# 1_main.net
KiCad netlist of a schematic drawn in Altium Designer
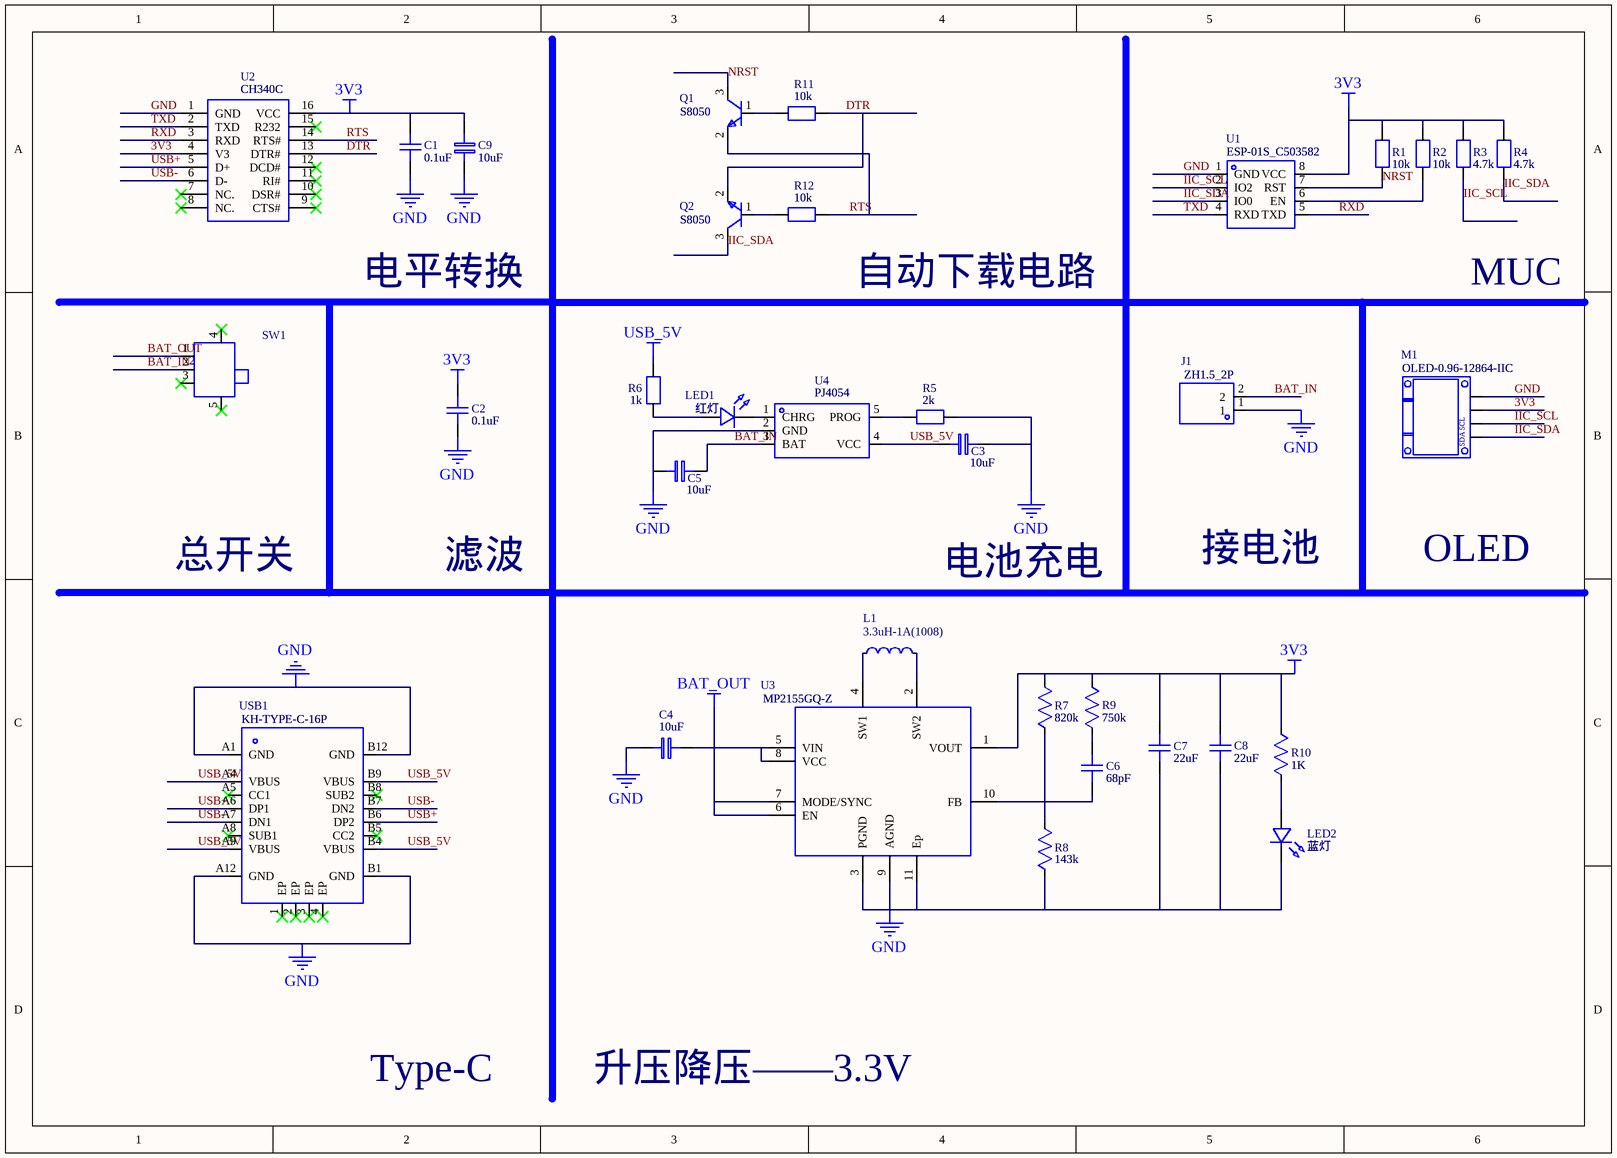
[diagram p0: 1_main.schdoc]

(export (version "E")
  (design (tool "Eeschema 10.0.6"))
  (components
    (comp (ref "C1")
      (value "0.1uF")
      (fields (field (name "NAME") "0.1uF"))
      (libsource (lib "altium-import") (part "root_1_0.1uF_"))
    )
    (comp (ref "C2")
      (value "0.1uF")
      (fields (field (name "NAME") "0.1uF"))
      (libsource (lib "altium-import") (part "root_1_0.1uF_C0805_"))
    )
    (comp (ref "C3")
      (value "10uF")
      (fields (field (name "NAME") "10uF"))
      (libsource (lib "altium-import") (part "root_0_10uF_"))
    )
    (comp (ref "C4")
      (value "10uF")
      (fields (field (name "NAME") "10uF"))
      (libsource (lib "altium-import") (part "root_0_10uF_C0805_"))
    )
    (comp (ref "C5")
      (value "10uF")
      (fields (field (name "NAME") "10uF"))
      (libsource (lib "altium-import") (part "root_0_10uF_C0805_"))
    )
    (comp (ref "C6")
      (value "68pF")
      (fields (field (name "NAME") "68pF"))
      (libsource (lib "altium-import") (part "root_1_68pF_"))
    )
    (comp (ref "C7")
      (value "22uF")
      (fields (field (name "NAME") "22uF"))
      (libsource (lib "altium-import") (part "root_1_22uF_"))
    )
    (comp (ref "C8")
      (value "22uF")
      (fields (field (name "NAME") "22uF"))
      (libsource (lib "altium-import") (part "root_1_22uF_C0805_"))
    )
    (comp (ref "C9")
      (value "10uF")
      (fields (field (name "NAME") "10uF"))
      (libsource (lib "altium-import") (part "root_1_10uF_C0805_"))
    )
    (comp (ref "J1")
      (value "ZH1.5_2P")
      (fields (field (name "NAME") "ZH1.5_2P") (field (name "MANUFACTURER") "JST Sales America"))
      (libsource (lib "altium-import") (part "root_0_ZH1.5_2P_"))
    )
    (comp (ref "L1")
      (value "3.3uH-1A(1008)")
      (description "电感值:10nH;精度:±5%;额定电流:300mA;饱和电流(Isat):-;直流电阻(DCR):400mΩ;")
      (libsource (lib "altium-import") (part "root_0_L_0402_"))
    )
    (comp (ref "LED1")
      (value "红灯")
      (fields
        (field (name "NAME") "红灯")
        (field (name "MANUFACTURER") "EVERLIGHT(台湾亿光)")
        (field (name "MANUFACTURER PART") "17-21SURC/S530-A3/TR8")
      )
      (libsource (lib "altium-import") (part "root_2_红灯_"))
    )
    (comp (ref "LED2")
      (value "蓝灯")
      (fields
        (field (name "NAME") "蓝灯")
        (field (name "MANUFACTURER") "方舟 ARKLED")
        (field (name "MANUFACTURER PART") "D-B080508B1-KS2")
      )
      (libsource (lib "altium-import") (part "root_3_蓝灯_"))
    )
    (comp (ref "M1")
      (value "OLED-0.96-12864-IIC")
      (fields (field (name "NAME") "OLED-0.96-12864-IIC"))
      (libsource (lib "altium-import") (part "root_3_OLED-0.96-12864-IIC_"))
    )
    (comp (ref "Q1")
      (value "S8050")
      (fields (field (name "NAME") "S8050") (field (name "MANUFACTURER") "FOSAN(富信)"))
      (libsource (lib "altium-import") (part "root_0_S8050_"))
    )
    (comp (ref "Q2")
      (value "S8050")
      (fields (field (name "NAME") "S8050") (field (name "MANUFACTURER") "FOSAN(富信)"))
      (libsource (lib "altium-import") (part "root_0_S8050_SOT-23-3_L2.9-W1.3-P1.90-LS2.4-BR_"))
    )
    (comp (ref "R1")
      (value "10k")
      (fields (field (name "NAME") "10k"))
      (libsource (lib "altium-import") (part "root_1_10k_R0805_"))
    )
    (comp (ref "R2")
      (value "10k")
      (fields (field (name "NAME") "10k"))
      (libsource (lib "altium-import") (part "root_1_10k_"))
    )
    (comp (ref "R3")
      (value "4.7k")
      (fields (field (name "NAME") "4.7k"))
      (libsource (lib "altium-import") (part "root_1_4.7k_"))
    )
    (comp (ref "R4")
      (value "4.7k")
      (fields (field (name "NAME") "4.7k"))
      (libsource (lib "altium-import") (part "root_1_4.7k_R0805_"))
    )
    (comp (ref "R5")
      (value "2k")
      (fields (field (name "NAME") "2k"))
      (libsource (lib "altium-import") (part "root_0_2k_"))
    )
    (comp (ref "R6")
      (value "1k")
      (fields (field (name "NAME") "1k"))
      (libsource (lib "altium-import") (part "root_1_1k_"))
    )
    (comp (ref "R7")
      (value "820k")
      (fields (field (name "NAME") "820k"))
      (libsource (lib "altium-import") (part "root_1_820k_"))
    )
    (comp (ref "R8")
      (value "143k")
      (fields (field (name "NAME") "143k"))
      (libsource (lib "altium-import") (part "root_1_143k_"))
    )
    (comp (ref "R9")
      (value "750k")
      (fields (field (name "NAME") "750k"))
      (libsource (lib "altium-import") (part "root_1_750k_"))
    )
    (comp (ref "R10")
      (value "1K")
      (fields (field (name "NAME") "1K"))
      (libsource (lib "altium-import") (part "root_1_1K_R0805_"))
    )
    (comp (ref "R11")
      (value "10k")
      (fields (field (name "NAME") "10k"))
      (libsource (lib "altium-import") (part "root_0_10k_R0805_"))
    )
    (comp (ref "R12")
      (value "10k")
      (fields (field (name "NAME") "10k"))
      (libsource (lib "altium-import") (part "root_0_10k_R0805_"))
    )
    (comp (ref "SW1")
      (value "~")
      (fields
        (field (name "MANUFACTURER") "SHOU HAN(首韩)")
        (field (name "MANUFACTURER PART") "SK12D07VG6")
        (field (name "NUMBER") "2")
      )
      (libsource (lib "altium-import") (part "root_3_mirrored_SK12D07VG6_"))
    )
    (comp (ref "U1")
      (value "ESP-01S_C503582")
      (fields
        (field (name "NAME") "ESP-01S_C503582")
        (field (name "MANUFACTURER") "Ai-Thinker")
        (field (name "MANUFACTURER PART") "ESP-01S")
      )
      (libsource (lib "altium-import") (part "root_0_ESP-01S_C503582_"))
    )
    (comp (ref "U2")
      (value "CH340C")
      (fields (field (name "NAME") "CH340C") (field (name "MANUFACTURER") "WCH"))
      (libsource (lib "altium-import") (part "root_0_CH340C_"))
    )
    (comp (ref "U3")
      (value "MP2155GQ-Z")
      (fields (field (name "NAME") "MP2155GQ-Z") (field (name "MANUFACTURER") "MPS"))
      (libsource (lib "altium-import") (part "root_0_MP2155GQ-Z_"))
    )
    (comp (ref "U4")
      (value "PJ4054")
      (fields (field (name "NAME") "PJ4054") (field (name "MANUFACTURER") "PJ(Pingjingsemi)"))
      (libsource (lib "altium-import") (part "root_0_PJ4054_"))
    )
    (comp (ref "USB1")
      (value "KH-TYPE-C-16P")
      (fields (field (name "NAME") "KH-TYPE-C-16P") (field (name "MANUFACTURER") "Shenzhen Kinghelm Elec"))
      (libsource (lib "altium-import") (part "root_0_KH-TYPE-C-16P_"))
    )
  )
  (nets
    (net (code "1") (name "/BAT_IN") (class "Default")
      (node (ref "C5") (pin "2") (pinfunction "2_2") (pintype "passive"))
      (node (ref "J1") (pin "2") (pinfunction "2_2") (pintype "passive"))
      (node (ref "SW1") (pin "2") (pinfunction "2_2") (pintype "passive"))
      (node (ref "U4") (pin "3") (pinfunction "BAT_3") (pintype "passive"))
    )
    (net (code "2") (name "/DTR") (class "Default")
      (node (ref "Q2") (pin "2") (pintype "passive"))
      (node (ref "R11") (pin "2") (pinfunction "2_2") (pintype "passive"))
      (node (ref "U2") (pin "13") (pinfunction "DTR#_13") (pintype "passive"))
    )
    (net (code "3") (name "/IIC_SCL") (class "Default")
      (node (ref "M1") (pin "3") (pinfunction "SCL_3") (pintype "passive"))
      (node (ref "R3") (pin "1") (pinfunction "1_1") (pintype "passive"))
      (node (ref "U1") (pin "2") (pinfunction "IO2_2") (pintype "passive"))
    )
    (net (code "4") (name "/IIC_SDA") (class "Default")
      (node (ref "M1") (pin "4") (pinfunction "SDA_4") (pintype "passive"))
      (node (ref "Q2") (pin "3") (pintype "passive"))
      (node (ref "R4") (pin "1") (pinfunction "1_1") (pintype "passive"))
      (node (ref "U1") (pin "3") (pinfunction "IO0_3") (pintype "passive"))
    )
    (net (code "5") (name "/NRST") (class "Default")
      (node (ref "Q1") (pin "3") (pintype "passive"))
      (node (ref "R1") (pin "1") (pinfunction "1_1") (pintype "passive"))
      (node (ref "U1") (pin "7") (pinfunction "RST_7") (pintype "passive"))
    )
    (net (code "6") (name "/RTS") (class "Default")
      (node (ref "Q1") (pin "2") (pintype "passive"))
      (node (ref "R12") (pin "2") (pinfunction "2_2") (pintype "passive"))
      (node (ref "U2") (pin "14") (pinfunction "RTS#_14") (pintype "passive"))
    )
    (net (code "7") (name "/RXD") (class "Default")
      (node (ref "U1") (pin "5") (pinfunction "TXD_5") (pintype "passive"))
      (node (ref "U2") (pin "3") (pinfunction "RXD_3") (pintype "passive"))
    )
    (net (code "8") (name "/TXD") (class "Default")
      (node (ref "U1") (pin "4") (pinfunction "RXD_4") (pintype "passive"))
      (node (ref "U2") (pin "2") (pinfunction "TXD_2") (pintype "passive"))
    )
    (net (code "9") (name "/USB+") (class "Default")
      (node (ref "U2") (pin "5") (pinfunction "D+_5") (pintype "passive"))
      (node (ref "USB1") (pin "A6") (pinfunction "DP1_A6") (pintype "passive"))
      (node (ref "USB1") (pin "B6") (pinfunction "DP2_B6") (pintype "passive"))
    )
    (net (code "10") (name "/USB-") (class "Default")
      (node (ref "U2") (pin "6") (pinfunction "D-_6") (pintype "passive"))
      (node (ref "USB1") (pin "A7") (pinfunction "DN1_A7") (pintype "passive"))
      (node (ref "USB1") (pin "B7") (pinfunction "DN2_B7") (pintype "passive"))
    )
    (net (code "11") (name "3V3") (class "Default")
      (node (ref "C1") (pin "2") (pinfunction "2_2") (pintype "passive"))
      (node (ref "C2") (pin "2") (pinfunction "2_2") (pintype "passive"))
      (node (ref "C7") (pin "2") (pinfunction "2_2") (pintype "passive"))
      (node (ref "C8") (pin "2") (pinfunction "2_2") (pintype "passive"))
      (node (ref "C9") (pin "2") (pinfunction "2_2") (pintype "passive"))
      (node (ref "M1") (pin "2") (pinfunction "VCC_2") (pintype "passive"))
      (node (ref "R1") (pin "2") (pinfunction "2_2") (pintype "passive"))
      (node (ref "R10") (pin "2") (pinfunction "2_2") (pintype "passive"))
      (node (ref "R2") (pin "2") (pinfunction "2_2") (pintype "passive"))
      (node (ref "R3") (pin "2") (pinfunction "2_2") (pintype "passive"))
      (node (ref "R4") (pin "2") (pinfunction "2_2") (pintype "passive"))
      (node (ref "R7") (pin "2") (pinfunction "2_2") (pintype "passive"))
      (node (ref "R9") (pin "2") (pinfunction "2_2") (pintype "passive"))
      (node (ref "U1") (pin "8") (pinfunction "VCC_8") (pintype "passive"))
      (node (ref "U2") (pin "16") (pinfunction "VCC_16") (pintype "passive"))
      (node (ref "U2") (pin "4") (pinfunction "V3_4") (pintype "passive"))
      (node (ref "U3") (pin "1") (pinfunction "VOUT_1") (pintype "passive"))
    )
    (net (code "12") (name "BAT_OUT") (class "Default")
      (node (ref "C4") (pin "2") (pinfunction "2_2") (pintype "passive"))
      (node (ref "SW1") (pin "1") (pinfunction "1_1") (pintype "passive"))
      (node (ref "U3") (pin "5") (pinfunction "VIN_5") (pintype "passive"))
      (node (ref "U3") (pin "6") (pinfunction "EN_6") (pintype "passive"))
      (node (ref "U3") (pin "7") (pinfunction "MODE/SYNC_7") (pintype "passive"))
      (node (ref "U3") (pin "8") (pinfunction "VCC_8") (pintype "passive"))
    )
    (net (code "13") (name "GND") (class "Default")
      (node (ref "C1") (pin "1") (pinfunction "1_1") (pintype "passive"))
      (node (ref "C2") (pin "1") (pinfunction "1_1") (pintype "passive"))
      (node (ref "C3") (pin "2") (pinfunction "2_2") (pintype "passive"))
      (node (ref "C4") (pin "1") (pinfunction "1_1") (pintype "passive"))
      (node (ref "C5") (pin "1") (pinfunction "1_1") (pintype "passive"))
      (node (ref "C7") (pin "1") (pinfunction "1_1") (pintype "passive"))
      (node (ref "C8") (pin "1") (pinfunction "1_1") (pintype "passive"))
      (node (ref "C9") (pin "1") (pinfunction "1_1") (pintype "passive"))
      (node (ref "J1") (pin "1") (pinfunction "1_1") (pintype "passive"))
      (node (ref "LED2") (pin "2") (pinfunction "2_2") (pintype "passive"))
      (node (ref "M1") (pin "1") (pinfunction "GND_1") (pintype "passive"))
      (node (ref "R5") (pin "2") (pinfunction "2_2") (pintype "passive"))
      (node (ref "R8") (pin "1") (pinfunction "1_1") (pintype "passive"))
      (node (ref "U1") (pin "1") (pinfunction "GND_1") (pintype "passive"))
      (node (ref "U2") (pin "1") (pinfunction "GND_1") (pintype "passive"))
      (node (ref "U3") (pin "11") (pinfunction "Ep_11") (pintype "passive"))
      (node (ref "U3") (pin "3") (pinfunction "PGND_3") (pintype "passive"))
      (node (ref "U3") (pin "9") (pinfunction "AGND_9") (pintype "passive"))
      (node (ref "U4") (pin "2") (pinfunction "GND_2") (pintype "passive"))
      (node (ref "USB1") (pin "A1") (pinfunction "GND_A1") (pintype "passive"))
      (node (ref "USB1") (pin "A12") (pinfunction "GND_A12") (pintype "passive"))
      (node (ref "USB1") (pin "B1") (pinfunction "GND_B1") (pintype "passive"))
      (node (ref "USB1") (pin "B12") (pinfunction "GND_B12") (pintype "passive"))
    )
    (net (code "14") (name "Net-(C6-Pad2)") (class "Default")
      (node (ref "C6") (pin "2") (pinfunction "2_2") (pintype "passive"))
      (node (ref "R9") (pin "1") (pinfunction "1_1") (pintype "passive"))
    )
    (net (code "15") (name "Net-(LED1-Pad1)") (class "Default")
      (node (ref "LED1") (pin "1") (pinfunction "1_1") (pintype "passive"))
      (node (ref "R6") (pin "1") (pinfunction "1_1") (pintype "passive"))
    )
    (net (code "16") (name "Net-(LED2-Pad1)") (class "Default")
      (node (ref "LED2") (pin "1") (pinfunction "1_1") (pintype "passive"))
      (node (ref "R10") (pin "1") (pinfunction "1_1") (pintype "passive"))
    )
    (net (code "17") (name "Net-(Q1-Pad1)") (class "Default")
      (node (ref "Q1") (pin "1") (pintype "passive"))
      (node (ref "R11") (pin "1") (pinfunction "1_1") (pintype "passive"))
    )
    (net (code "18") (name "Net-(Q2-Pad1)") (class "Default")
      (node (ref "Q2") (pin "1") (pintype "passive"))
      (node (ref "R12") (pin "1") (pinfunction "1_1") (pintype "passive"))
    )
    (net (code "19") (name "Net-(U1-EN)") (class "Default")
      (node (ref "R2") (pin "1") (pinfunction "1_1") (pintype "passive"))
      (node (ref "U1") (pin "6") (pinfunction "EN_6") (pintype "passive"))
    )
    (net (code "20") (name "Net-(U3-FB)") (class "Default")
      (node (ref "C6") (pin "1") (pinfunction "1_1") (pintype "passive"))
      (node (ref "R7") (pin "1") (pinfunction "1_1") (pintype "passive"))
      (node (ref "R8") (pin "2") (pinfunction "2_2") (pintype "passive"))
      (node (ref "U3") (pin "10") (pinfunction "FB_10") (pintype "passive"))
    )
    (net (code "21") (name "Net-(U3-SW1)") (class "Default")
      (node (ref "L1") (pin "1") (pinfunction "1_1") (pintype "passive"))
      (node (ref "U3") (pin "4") (pinfunction "SW1_4") (pintype "passive"))
    )
    (net (code "22") (name "Net-(U3-SW2)") (class "Default")
      (node (ref "L1") (pin "2") (pinfunction "2_2") (pintype "passive"))
      (node (ref "U3") (pin "2") (pinfunction "SW2_2") (pintype "passive"))
    )
    (net (code "23") (name "Net-(U4-CHRG)") (class "Default")
      (node (ref "LED1") (pin "2") (pinfunction "2_2") (pintype "passive"))
      (node (ref "U4") (pin "1") (pinfunction "CHRG_1") (pintype "passive"))
    )
    (net (code "24") (name "Net-(U4-PROG)") (class "Default")
      (node (ref "R5") (pin "1") (pinfunction "1_1") (pintype "passive"))
      (node (ref "U4") (pin "5") (pinfunction "PROG_5") (pintype "passive"))
    )
    (net (code "25") (name "USB_5V") (class "Default")
      (node (ref "C3") (pin "1") (pinfunction "1_1") (pintype "passive"))
      (node (ref "R6") (pin "2") (pinfunction "2_2") (pintype "passive"))
      (node (ref "U4") (pin "4") (pinfunction "VCC_4") (pintype "passive"))
      (node (ref "USB1") (pin "A4") (pinfunction "VBUS_A4") (pintype "passive"))
      (node (ref "USB1") (pin "A9") (pinfunction "VBUS_A9") (pintype "passive"))
      (node (ref "USB1") (pin "B4") (pinfunction "VBUS_B4") (pintype "passive"))
      (node (ref "USB1") (pin "B9") (pinfunction "VBUS_B9") (pintype "passive"))
    )
    (net (code "26") (name "unconnected-(SW1-Pad3)") (class "Default")
      (node (ref "SW1") (pin "3") (pinfunction "3_3") (pintype "passive+no_connect"))
    )
    (net (code "27") (name "unconnected-(SW1-Pad4)") (class "Default")
      (node (ref "SW1") (pin "4") (pinfunction "4_4") (pintype "passive+no_connect"))
    )
    (net (code "28") (name "unconnected-(SW1-Pad5)") (class "Default")
      (node (ref "SW1") (pin "5") (pinfunction "5_5") (pintype "passive+no_connect"))
    )
    (net (code "29") (name "unconnected-(U2-CTS#-Pad9)") (class "Default")
      (node (ref "U2") (pin "9") (pinfunction "CTS#_9") (pintype "passive+no_connect"))
    )
    (net (code "30") (name "unconnected-(U2-DCD#-Pad12)") (class "Default")
      (node (ref "U2") (pin "12") (pinfunction "DCD#_12") (pintype "passive+no_connect"))
    )
    (net (code "31") (name "unconnected-(U2-DSR#-Pad10)") (class "Default")
      (node (ref "U2") (pin "10") (pinfunction "DSR#_10") (pintype "passive+no_connect"))
    )
    (net (code "32") (name "unconnected-(U2-NC.-Pad7)") (class "Default")
      (node (ref "U2") (pin "7") (pinfunction "NC._7") (pintype "passive+no_connect"))
    )
    (net (code "33") (name "unconnected-(U2-NC.-Pad8)") (class "Default")
      (node (ref "U2") (pin "8") (pinfunction "NC._8") (pintype "passive+no_connect"))
    )
    (net (code "34") (name "unconnected-(U2-R232-Pad15)") (class "Default")
      (node (ref "U2") (pin "15") (pinfunction "R232_15") (pintype "passive+no_connect"))
    )
    (net (code "35") (name "unconnected-(U2-RI#-Pad11)") (class "Default")
      (node (ref "U2") (pin "11") (pinfunction "RI#_11") (pintype "passive+no_connect"))
    )
    (net (code "36") (name "unconnected-(USB1-CC1-PadA5)") (class "Default")
      (node (ref "USB1") (pin "A5") (pinfunction "CC1_A5") (pintype "passive+no_connect"))
    )
    (net (code "37") (name "unconnected-(USB1-CC2-PadB5)") (class "Default")
      (node (ref "USB1") (pin "B5") (pinfunction "CC2_B5") (pintype "passive+no_connect"))
    )
    (net (code "38") (name "unconnected-(USB1-EP-Pad1)") (class "Default")
      (node (ref "USB1") (pin "1") (pinfunction "EP_1") (pintype "passive+no_connect"))
    )
    (net (code "39") (name "unconnected-(USB1-EP-Pad2)") (class "Default")
      (node (ref "USB1") (pin "2") (pinfunction "EP_2") (pintype "passive+no_connect"))
    )
    (net (code "40") (name "unconnected-(USB1-EP-Pad3)") (class "Default")
      (node (ref "USB1") (pin "3") (pinfunction "EP_3") (pintype "passive+no_connect"))
    )
    (net (code "41") (name "unconnected-(USB1-EP-Pad4)") (class "Default")
      (node (ref "USB1") (pin "4") (pinfunction "EP_4") (pintype "passive+no_connect"))
    )
    (net (code "42") (name "unconnected-(USB1-SUB1-PadA8)") (class "Default")
      (node (ref "USB1") (pin "A8") (pinfunction "SUB1_A8") (pintype "passive+no_connect"))
    )
    (net (code "43") (name "unconnected-(USB1-SUB2-PadB8)") (class "Default")
      (node (ref "USB1") (pin "B8") (pinfunction "SUB2_B8") (pintype "passive+no_connect"))
    )
  )
)
